# ZP.net
KiCad netlist of a schematic drawn in Altium Designer
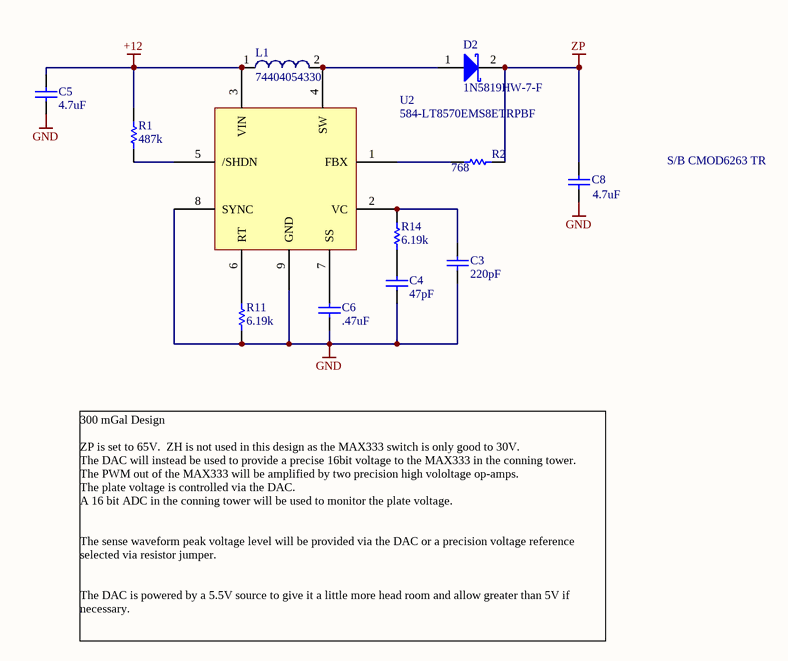
[diagram p0: ZP.SchDoc]

(export (version "E")
  (design (tool "Eeschema 10.0.6"))
  (components
    (comp (ref "C3")
      (value "220pF")
      (footprint "CAPC0402(1005)60_L")
      (description "CAP CER 0.1UF 10V X7R 0402")
      (libsource (lib "Altium Content Vault") (part "CMP-1034-00252-1"))
    )
    (comp (ref "C4")
      (value "47pF")
      (footprint "CAPC0402(1005)60_L")
      (description "CAP CER 0.1UF 10V X7R 0402")
      (libsource (lib "Altium Content Vault") (part "CMP-1034-00252-1"))
    )
    (comp (ref "C5")
      (value "4.7uF")
      (footprint "CAPC0805(2012)155_L")
      (libsource (lib "Altium Content Vault") (part "CMP-1036-04882-1"))
    )
    (comp (ref "C6")
      (value ".47uF")
      (footprint "CAPC0402(1005)60_L")
      (description "CAP CER 0.1UF 10V X7R 0402")
      (libsource (lib "Altium Content Vault") (part "CMP-1034-00252-1"))
    )
    (comp (ref "C8")
      (value "CAP CER 1UF 25V X7R 0805")
      (footprint "CAPC0805(2012)155_L")
      (fields
        (field (name "MANUFACTURER") "Murata Electronics North America")
        (field (name "MANUFACTURER PART NUMBER") "GRM21BR71E105KA99L")
        (field (name "CAPACITANCE") "4.7uF")
        (field (name "TOLERANCE") "±10%")
      )
      (libsource (lib "Altium Content Vault") (part "CMP-1036-04882-1"))
    )
    (comp (ref "D2")
      (value "1N5819HW-7-F")
      (footprint "DIOD-SOD-123-2_V")
      (fields (field (name "MANUFACTURER") "Diodes Inc"))
      (libsource (lib "Altium Content Vault") (part "DIOD-DSKY-A1K2-2"))
    )
    (comp (ref "L1")
      (value "74404054330")
      (footprint "WE-LQS 5040")
      (description "WE-LQS SMD Power Inductor, L=33.0 µH")
      (fields (field (name "MANUFACTURER") "Wuerth Elektronik"))
      (libsource (lib "Altium Content Vault") (part "WE-IND-INDUCTOR-2"))
    )
    (comp (ref "R1")
      (value "487k")
      (footprint "RESC0402(1005)_M")
      (libsource (lib "Altium Content Vault") (part "CMP-1011-00463-1"))
    )
    (comp (ref "R2")
      (value "768")
      (footprint "RESC0402(1005)_M")
      (libsource (lib "Altium Content Vault") (part "CMP-1011-00463-1"))
    )
    (comp (ref "R11")
      (value "6.19k")
      (footprint "RESC0402(1005)_M")
      (libsource (lib "Altium Content Vault") (part "CMP-1011-00463-1"))
    )
    (comp (ref "R14")
      (value "6.19k")
      (footprint "RESC0402(1005)_M")
      (libsource (lib "Altium Content Vault") (part "CMP-1011-00463-1"))
    )
    (comp (ref "U2")
      (value "LT8570")
      (footprint "LT8570-MSOP")
      (description "IC REG MULT CONFIG INV ADJ 8MSOP")
      (fields (field (name "SUPPLIER PART NUMBER 1") "584-LT8570EMS8ETRPBF"))
      (libsource (lib "ZLS_Schematic_lib") (part "LT8570"))
    )
  )
  (nets
    (net (code "1") (name "+12") (class "Default")
      (node (ref "C5") (pin "2") (pinfunction "2_2") (pintype "passive"))
      (node (ref "L1") (pin "1") (pinfunction "1_1") (pintype "passive"))
      (node (ref "R1") (pin "1") (pinfunction "1_1") (pintype "passive"))
      (node (ref "U2") (pin "3") (pinfunction "VIN_3") (pintype "passive"))
    )
    (net (code "2") (name "GND") (class "Default")
      (node (ref "C3") (pin "1") (pinfunction "1_1") (pintype "passive"))
      (node (ref "C4") (pin "1") (pinfunction "1_1") (pintype "passive"))
      (node (ref "C5") (pin "1") (pinfunction "1_1") (pintype "passive"))
      (node (ref "C6") (pin "1") (pinfunction "1_1") (pintype "passive"))
      (node (ref "C8") (pin "1") (pinfunction "1_1") (pintype "passive"))
      (node (ref "R11") (pin "2") (pinfunction "2_2") (pintype "passive"))
      (node (ref "U2") (pin "8") (pinfunction "SYNC_8") (pintype "passive"))
      (node (ref "U2") (pin "9") (pinfunction "GND_9") (pintype "passive"))
    )
    (net (code "3") (name "Net-(C4-Pad2)") (class "Default")
      (node (ref "C4") (pin "2") (pinfunction "2_2") (pintype "passive"))
      (node (ref "R14") (pin "2") (pinfunction "2_2") (pintype "passive"))
    )
    (net (code "4") (name "Net-(D2-A)") (class "Default")
      (node (ref "D2") (pin "1") (pinfunction "A_1") (pintype "passive"))
      (node (ref "L1") (pin "2") (pinfunction "2_2") (pintype "passive"))
      (node (ref "U2") (pin "4") (pinfunction "SW_4") (pintype "passive"))
    )
    (net (code "5") (name "Net-(U2-FBX)") (class "Default")
      (node (ref "R2") (pin "1") (pinfunction "1_1") (pintype "passive"))
      (node (ref "U2") (pin "1") (pinfunction "FBX_1") (pintype "passive"))
    )
    (net (code "6") (name "Net-(U2-RT)") (class "Default")
      (node (ref "R11") (pin "1") (pinfunction "1_1") (pintype "passive"))
      (node (ref "U2") (pin "6") (pinfunction "RT_6") (pintype "passive"))
    )
    (net (code "7") (name "Net-(U2-SS)") (class "Default")
      (node (ref "C6") (pin "2") (pinfunction "2_2") (pintype "passive"))
      (node (ref "U2") (pin "7") (pinfunction "SS_7") (pintype "passive"))
    )
    (net (code "8") (name "Net-(U2-VC)") (class "Default")
      (node (ref "C3") (pin "2") (pinfunction "2_2") (pintype "passive"))
      (node (ref "R14") (pin "1") (pinfunction "1_1") (pintype "passive"))
      (node (ref "U2") (pin "2") (pinfunction "VC_2") (pintype "passive"))
    )
    (net (code "9") (name "Net-(U2-{slash}SHDN)") (class "Default")
      (node (ref "R1") (pin "2") (pinfunction "2_2") (pintype "passive"))
      (node (ref "U2") (pin "5") (pinfunction "/SHDN_5") (pintype "passive"))
    )
    (net (code "10") (name "ZP") (class "Default")
      (node (ref "C8") (pin "2") (pinfunction "2_2") (pintype "passive"))
      (node (ref "D2") (pin "2") (pinfunction "K_2") (pintype "passive"))
      (node (ref "R2") (pin "2") (pinfunction "2_2") (pintype "passive"))
    )
  )
)
